# Tripple-LED.net
KiCad netlist of a schematic drawn in EAGLE
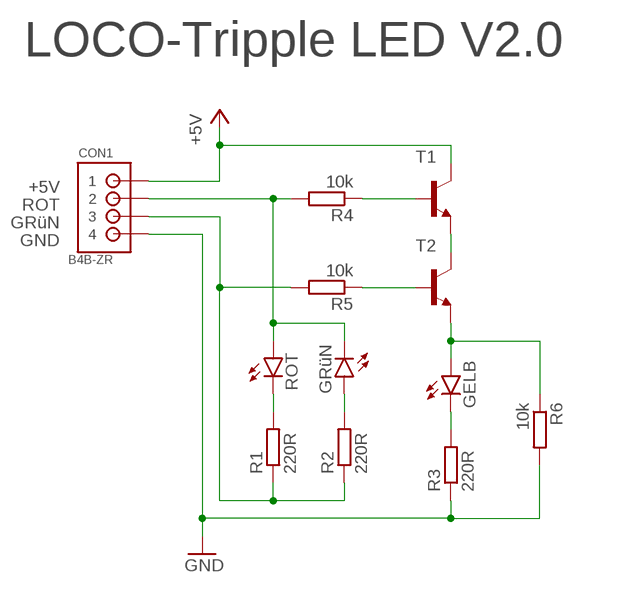
[diagram p0: schematic, sheet 1]

(export (version "E")
  (design (tool "Eeschema 10.0.6"))
  (components
    (comp (ref "CON1")
      (value "B4B-ZR")
      (footprint "eagle-import:B4B-ZR")
      (libsource (lib "eagle-import") (part "B4B-ZR"))
    )
    (comp (ref "GELB")
      (value "LED5MM")
      (footprint "eagle-import:LED5MM")
      (libsource (lib "eagle-import") (part "LED5MM"))
    )
    (comp (ref "GRüN")
      (value "LED5MM")
      (footprint "eagle-import:LED5MM")
      (libsource (lib "eagle-import") (part "LED5MM"))
    )
    (comp (ref "R1")
      (value "220R")
      (footprint "eagle-import:R0402")
      (libsource (lib "eagle-import") (part "R-EU_R0402"))
    )
    (comp (ref "R2")
      (value "220R")
      (footprint "eagle-import:R0402")
      (libsource (lib "eagle-import") (part "R-EU_R0402"))
    )
    (comp (ref "R3")
      (value "220R")
      (footprint "eagle-import:R0402")
      (libsource (lib "eagle-import") (part "R-EU_R0402"))
    )
    (comp (ref "R4")
      (value "10k")
      (footprint "eagle-import:R0402")
      (libsource (lib "eagle-import") (part "R-EU_R0402"))
    )
    (comp (ref "R5")
      (value "10k")
      (footprint "eagle-import:R0402")
      (libsource (lib "eagle-import") (part "R-EU_R0402"))
    )
    (comp (ref "R6")
      (value "10k")
      (footprint "eagle-import:R0402")
      (libsource (lib "eagle-import") (part "R-EU_R0402"))
    )
    (comp (ref "ROT")
      (value "LED5MM")
      (footprint "eagle-import:LED5MM")
      (libsource (lib "eagle-import") (part "LED5MM"))
    )
    (comp (ref "T1")
      (value "-NPN-SOT23-EBC")
      (footprint "eagle-import:SOT23-EBC")
      (libsource (lib "eagle-import") (part "-NPN-SOT23-EBC"))
    )
    (comp (ref "T2")
      (value "-NPN-SOT23-EBC")
      (footprint "eagle-import:SOT23-EBC")
      (libsource (lib "eagle-import") (part "-NPN-SOT23-EBC"))
    )
  )
  (nets
    (net (code "1") (name "+5V") (class "Default")
      (node (ref "CON1") (pin "1") (pinfunction "1_1") (pintype "bidirectional"))
      (node (ref "T1") (pin "C") (pinfunction "C_C") (pintype "passive"))
    )
    (net (code "2") (name "/GRüN") (class "Default")
      (node (ref "CON1") (pin "3") (pinfunction "3_3") (pintype "bidirectional"))
      (node (ref "R1") (pin "1") (pinfunction "1_1") (pintype "passive"))
      (node (ref "R2") (pin "1") (pinfunction "1_1") (pintype "passive"))
      (node (ref "R5") (pin "2") (pinfunction "2_2") (pintype "passive"))
    )
    (net (code "3") (name "/ROT") (class "Default")
      (node (ref "CON1") (pin "2") (pinfunction "2_2") (pintype "bidirectional"))
      (node (ref "GRüN") (pin "K") (pinfunction "C_K") (pintype "passive"))
      (node (ref "R4") (pin "2") (pinfunction "2_2") (pintype "passive"))
      (node (ref "ROT") (pin "A") (pinfunction "A_A") (pintype "passive"))
    )
    (net (code "4") (name "GND") (class "Default")
      (node (ref "CON1") (pin "4") (pinfunction "4_4") (pintype "bidirectional"))
      (node (ref "R3") (pin "1") (pinfunction "1_1") (pintype "passive"))
      (node (ref "R6") (pin "2") (pinfunction "2_2") (pintype "passive"))
    )
    (net (code "5") (name "Net-(GELB-C)") (class "Default")
      (node (ref "GELB") (pin "K") (pinfunction "C_K") (pintype "passive"))
      (node (ref "R3") (pin "2") (pinfunction "2_2") (pintype "passive"))
    )
    (net (code "6") (name "Net-(GELB-PadA)") (class "Default")
      (node (ref "GELB") (pin "A") (pinfunction "A_A") (pintype "passive"))
      (node (ref "R6") (pin "1") (pinfunction "1_1") (pintype "passive"))
      (node (ref "T2") (pin "E") (pinfunction "E_E") (pintype "passive"))
    )
    (net (code "7") (name "Net-(GRüN-PadA)") (class "Default")
      (node (ref "GRüN") (pin "A") (pinfunction "A_A") (pintype "passive"))
      (node (ref "R2") (pin "2") (pinfunction "2_2") (pintype "passive"))
    )
    (net (code "8") (name "Net-(R4-Pad1)") (class "Default")
      (node (ref "R4") (pin "1") (pinfunction "1_1") (pintype "passive"))
      (node (ref "T1") (pin "B") (pinfunction "B_B") (pintype "passive"))
    )
    (net (code "9") (name "Net-(R5-Pad1)") (class "Default")
      (node (ref "R5") (pin "1") (pinfunction "1_1") (pintype "passive"))
      (node (ref "T2") (pin "B") (pinfunction "B_B") (pintype "passive"))
    )
    (net (code "10") (name "Net-(ROT-C)") (class "Default")
      (node (ref "R1") (pin "2") (pinfunction "2_2") (pintype "passive"))
      (node (ref "ROT") (pin "K") (pinfunction "C_K") (pintype "passive"))
    )
    (net (code "11") (name "Net-(T1-PadE)") (class "Default")
      (node (ref "T1") (pin "E") (pinfunction "E_E") (pintype "passive"))
      (node (ref "T2") (pin "C") (pinfunction "C_C") (pintype "passive"))
    )
  )
)
